# poweramp.net
KiCad netlist of a schematic drawn in Altium Designer
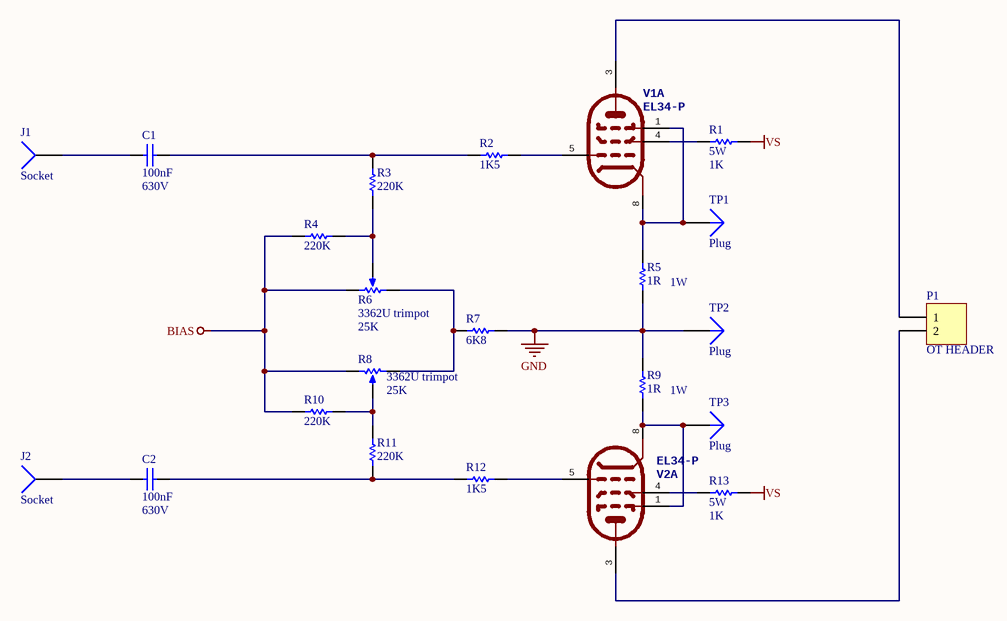
[diagram p0: poweramp.SchDoc]

(export (version "E")
  (design (tool "Eeschema 10.0.6"))
  (components
    (comp (ref "C1")
      (value "100nF")
      (footprint "ORANGE-DROP-100nF-600V")
      (description "Capacitor")
      (fields
        (field (name "VOLTAGE") "630V")
        (field (name "Comment") "Orange Drop Capacitor")
        (field (name "PUBLISHER") "Altium Limited")
      )
      (libsource (lib "capacitors") (part "Cap-Orange-DROP_600V"))
    )
    (comp (ref "C2")
      (value "100nF")
      (footprint "ORANGE-DROP-100nF-600V")
      (description "Capacitor")
      (fields
        (field (name "VOLTAGE") "630V")
        (field (name "Comment") "Orange Drop Capacitor")
        (field (name "PUBLISHER") "Altium Limited")
      )
      (libsource (lib "capacitors") (part "Cap-Orange-DROP_600V"))
    )
    (comp (ref "J1")
      (value "Socket")
      (footprint "PIN1")
      (fields (field (name "PUBLISHER") "Altium Limited"))
      (libsource (lib "Miscellaneous Connectors") (part "Socket"))
    )
    (comp (ref "J2")
      (value "Socket")
      (footprint "PIN1")
      (fields (field (name "PUBLISHER") "Altium Limited"))
      (libsource (lib "Miscellaneous Connectors") (part "Socket"))
    )
    (comp (ref "P1")
      (value "OT HEADER")
      (footprint "HDR2_pin")
      (description "Header, 2-Pin")
      (fields (field (name "PUBLISHER") "Altium Limited"))
      (libsource (lib "headers") (part "Header 2"))
    )
    (comp (ref "R1")
      (value "1K")
      (footprint "Resistor Vishay 5W 1k Power Wirewound")
      (description "Semiconductor Resistor")
      (fields
        (field (name "POWER") "5W")
        (field (name "Comment") "Wire Wound Power Resistor")
        (field (name "PUBLISHER") "Whitesheep Amps")
      )
      (libsource (lib "resistors") (part "Res Wire Wound Power Resistor 5W"))
    )
    (comp (ref "R2")
      (value "1K5")
      (footprint "AXIAL-0.6")
      (description "Semiconductor Resistor")
      (fields
        (field (name "POWER") "1/2W")
        (field (name "Comment") "Metal Film Resistor 1/2W")
        (field (name "PUBLISHER") "Whitesheep Amps")
      )
      (libsource (lib "resistors") (part "Res Metal Film 1/2W"))
    )
    (comp (ref "R3")
      (value "220K")
      (footprint "AXIAL-0.6")
      (description "Semiconductor Resistor")
      (fields
        (field (name "POWER") "1/2W")
        (field (name "Comment") "Metal Film Resistor 1/2W")
        (field (name "PUBLISHER") "Whitesheep Amps")
      )
      (libsource (lib "resistors") (part "Res Metal Film 1/2W"))
    )
    (comp (ref "R4")
      (value "220K")
      (footprint "AXIAL-0.6")
      (description "Semiconductor Resistor")
      (fields
        (field (name "POWER") "1/2W")
        (field (name "Comment") "Metal Film Resistor 1/2W")
        (field (name "PUBLISHER") "Whitesheep Amps")
      )
      (libsource (lib "resistors") (part "Res Metal Film 1/2W"))
    )
    (comp (ref "R5")
      (value "1R")
      (footprint "AXIAL-0.6")
      (description "Semiconductor Resistor")
      (fields
        (field (name "POWER") "1W")
        (field (name "Comment") "Metal Film Resistor 1/2W")
        (field (name "PUBLISHER") "Whitesheep Amps")
      )
      (libsource (lib "resistors") (part "Res Metal Film 1/2W"))
    )
    (comp (ref "R6")
      (value "3362U trimpot")
      (footprint "33262U trimpot")
      (description "3362U Timpot")
      (fields (field (name "ALTIUM_VALUE") "25K") (field (name "PUBLISHER") "Linda Hand Build Amplification"))
      (libsource (lib "potentiometers") (part "3362U trimpot"))
    )
    (comp (ref "R7")
      (value "6K8")
      (footprint "AXIAL-0.6")
      (description "Semiconductor Resistor")
      (fields
        (field (name "POWER") "1/2W")
        (field (name "Comment") "Metal Film Resistor 1/2W")
        (field (name "PUBLISHER") "Whitesheep Amps")
      )
      (libsource (lib "resistors") (part "Res Metal Film 1/2W"))
    )
    (comp (ref "R8")
      (value "3362U trimpot")
      (footprint "33262U trimpot")
      (description "3362U Timpot")
      (fields (field (name "ALTIUM_VALUE") "25K") (field (name "PUBLISHER") "Linda Hand Build Amplification"))
      (libsource (lib "potentiometers") (part "3362U trimpot"))
    )
    (comp (ref "R9")
      (value "1R")
      (footprint "AXIAL-0.6")
      (description "Semiconductor Resistor")
      (fields
        (field (name "POWER") "1W")
        (field (name "Comment") "Metal Film Resistor 1/2W")
        (field (name "PUBLISHER") "Whitesheep Amps")
      )
      (libsource (lib "resistors") (part "Res Metal Film 1/2W"))
    )
    (comp (ref "R10")
      (value "220K")
      (footprint "AXIAL-0.6")
      (description "Semiconductor Resistor")
      (fields
        (field (name "POWER") "1/2W")
        (field (name "Comment") "Metal Film Resistor 1/2W")
        (field (name "PUBLISHER") "Whitesheep Amps")
      )
      (libsource (lib "resistors") (part "Res Metal Film 1/2W"))
    )
    (comp (ref "R11")
      (value "220K")
      (footprint "AXIAL-0.6")
      (description "Semiconductor Resistor")
      (fields
        (field (name "POWER") "1/2W")
        (field (name "Comment") "Metal Film Resistor 1/2W")
        (field (name "PUBLISHER") "Whitesheep Amps")
      )
      (libsource (lib "resistors") (part "Res Metal Film 1/2W"))
    )
    (comp (ref "R12")
      (value "1K5")
      (footprint "AXIAL-0.6")
      (description "Semiconductor Resistor")
      (fields
        (field (name "POWER") "1/2W")
        (field (name "Comment") "Metal Film Resistor 1/2W")
        (field (name "PUBLISHER") "Whitesheep Amps")
      )
      (libsource (lib "resistors") (part "Res Metal Film 1/2W"))
    )
    (comp (ref "R13")
      (value "1K")
      (footprint "Resistor Vishay 5W 1k Power Wirewound")
      (description "Semiconductor Resistor")
      (fields
        (field (name "POWER") "5W")
        (field (name "Comment") "Wire Wound Power Resistor")
        (field (name "PUBLISHER") "Whitesheep Amps")
      )
      (libsource (lib "resistors") (part "Res Wire Wound Power Resistor 5W"))
    )
    (comp (ref "TP1")
      (value "Plug")
      (footprint "PIN1")
      (fields (field (name "PUBLISHER") "Altium Limited"))
      (libsource (lib "Miscellaneous Connectors") (part "Plug"))
    )
    (comp (ref "TP2")
      (value "Plug")
      (footprint "PIN1")
      (fields (field (name "PUBLISHER") "Altium Limited"))
      (libsource (lib "Miscellaneous Connectors") (part "Plug"))
    )
    (comp (ref "TP3")
      (value "Plug")
      (footprint "PIN1")
      (fields (field (name "PUBLISHER") "Altium Limited"))
      (libsource (lib "Miscellaneous Connectors") (part "Plug"))
    )
    (comp (ref "V1") (value "EL34-P") (footprint "OKTAL") (libsource (lib "") (part "EL34-P_1")))
    (comp (ref "V2") (value "EL34-P") (footprint "OKTAL") (libsource (lib "eagle_tubes_v6") (part "EL34-P")))
  )
  (nets
    (net (code "1") (name "BIAS") (class "Default")
      (node (ref "R10") (pin "1") (pinfunction "1_1") (pintype "passive"))
      (node (ref "R4") (pin "1") (pinfunction "1_1") (pintype "passive"))
      (node (ref "R6") (pin "2") (pinfunction "BOT_2") (pintype "passive"))
      (node (ref "R8") (pin "2") (pinfunction "BOT_2") (pintype "passive"))
    )
    (net (code "2") (name "GND") (class "Default")
      (node (ref "R5") (pin "1") (pinfunction "1_1") (pintype "passive"))
      (node (ref "R7") (pin "2") (pinfunction "2_2") (pintype "passive"))
      (node (ref "R9") (pin "2") (pinfunction "2_2") (pintype "passive"))
      (node (ref "TP2") (pin "1") (pinfunction "1_1") (pintype "passive"))
    )
    (net (code "3") (name "Net-(C1-Pad1)") (class "Default")
      (node (ref "C1") (pin "1") (pinfunction "1_1") (pintype "passive"))
      (node (ref "J1") (pin "1") (pinfunction "1_1") (pintype "passive"))
    )
    (net (code "4") (name "Net-(C1-Pad2)") (class "Default")
      (node (ref "C1") (pin "2") (pinfunction "2_2") (pintype "passive"))
      (node (ref "R2") (pin "1") (pinfunction "1_1") (pintype "passive"))
      (node (ref "R3") (pin "1") (pinfunction "1_1") (pintype "passive"))
    )
    (net (code "5") (name "Net-(C2-Pad1)") (class "Default")
      (node (ref "C2") (pin "1") (pinfunction "1_1") (pintype "passive"))
      (node (ref "J2") (pin "1") (pinfunction "1_1") (pintype "passive"))
    )
    (net (code "6") (name "Net-(C2-Pad2)") (class "Default")
      (node (ref "C2") (pin "2") (pinfunction "2_2") (pintype "passive"))
      (node (ref "R11") (pin "2") (pinfunction "2_2") (pintype "passive"))
      (node (ref "R12") (pin "1") (pinfunction "1_1") (pintype "passive"))
    )
    (net (code "7") (name "Net-(R6-TAP)") (class "Default")
      (node (ref "R3") (pin "2") (pinfunction "2_2") (pintype "passive"))
      (node (ref "R4") (pin "2") (pinfunction "2_2") (pintype "passive"))
      (node (ref "R6") (pin "3") (pinfunction "TAP_3") (pintype "passive"))
    )
    (net (code "8") (name "Net-(R6-TOP)") (class "Default")
      (node (ref "R6") (pin "1") (pinfunction "TOP_1") (pintype "passive"))
      (node (ref "R7") (pin "1") (pinfunction "1_1") (pintype "passive"))
      (node (ref "R8") (pin "1") (pinfunction "TOP_1") (pintype "passive"))
    )
    (net (code "9") (name "Net-(R8-TAP)") (class "Default")
      (node (ref "R10") (pin "2") (pinfunction "2_2") (pintype "passive"))
      (node (ref "R11") (pin "1") (pinfunction "1_1") (pintype "passive"))
      (node (ref "R8") (pin "3") (pinfunction "TAP_3") (pintype "passive"))
    )
    (net (code "10") (name "Net-(V1A-PA)") (class "Default")
      (node (ref "P1") (pin "1") (pinfunction "1_1") (pintype "passive"))
      (node (ref "V1") (pin "3") (pinfunction "PA_3") (pintype "passive"))
    )
    (net (code "11") (name "Net-(V1A-PBG)") (class "Default")
      (node (ref "R5") (pin "2") (pinfunction "2_2") (pintype "passive"))
      (node (ref "TP1") (pin "1") (pinfunction "1_1") (pintype "passive"))
      (node (ref "V1") (pin "1") (pinfunction "PBG_1") (pintype "passive"))
      (node (ref "V1") (pin "8") (pinfunction "PK_8") (pintype "passive"))
    )
    (net (code "12") (name "Net-(V1A-PG)") (class "Default")
      (node (ref "R2") (pin "2") (pinfunction "2_2") (pintype "passive"))
      (node (ref "V1") (pin "5") (pinfunction "PG_5") (pintype "passive"))
    )
    (net (code "13") (name "Net-(V1A-PSG)") (class "Default")
      (node (ref "R1") (pin "1") (pinfunction "1_1") (pintype "passive"))
      (node (ref "V1") (pin "4") (pinfunction "PSG_4") (pintype "passive"))
    )
    (net (code "14") (name "Net-(V2A-PA)") (class "Default")
      (node (ref "P1") (pin "2") (pinfunction "2_2") (pintype "passive"))
      (node (ref "V2") (pin "3") (pinfunction "PA_3") (pintype "passive"))
    )
    (net (code "15") (name "Net-(V2A-PBG)") (class "Default")
      (node (ref "R9") (pin "1") (pinfunction "1_1") (pintype "passive"))
      (node (ref "TP3") (pin "1") (pinfunction "1_1") (pintype "passive"))
      (node (ref "V2") (pin "1") (pinfunction "PBG_1") (pintype "passive"))
      (node (ref "V2") (pin "8") (pinfunction "PK_8") (pintype "passive"))
    )
    (net (code "16") (name "Net-(V2A-PG)") (class "Default")
      (node (ref "R12") (pin "2") (pinfunction "2_2") (pintype "passive"))
      (node (ref "V2") (pin "5") (pinfunction "PG_5") (pintype "passive"))
    )
    (net (code "17") (name "Net-(V2A-PSG)") (class "Default")
      (node (ref "R13") (pin "1") (pinfunction "1_1") (pintype "passive"))
      (node (ref "V2") (pin "4") (pinfunction "PSG_4") (pintype "passive"))
    )
    (net (code "18") (name "VS") (class "Default")
      (node (ref "R1") (pin "2") (pinfunction "2_2") (pintype "passive"))
      (node (ref "R13") (pin "2") (pinfunction "2_2") (pintype "passive"))
    )
  )
)
